# Power.net
KiCad netlist of a schematic drawn in Altium Designer
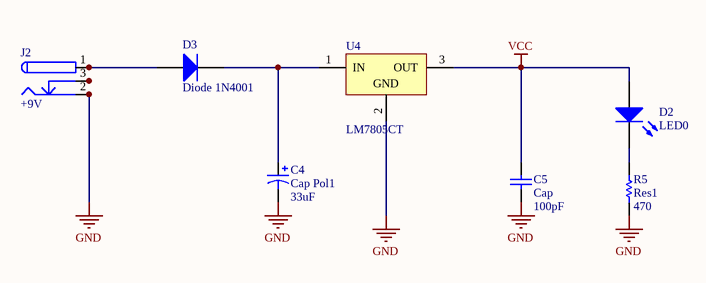
[diagram p0: Power.SchDoc]

(export (version "E")
  (design (tool "Eeschema 10.0.6"))
  (components
    (comp (ref "C4")
      (value "Cap Pol1")
      (footprint "RB7.6-15")
      (description "Polarized Capacitor (Radial)")
      (fields (field (name "ALTIUM_VALUE") "33uF") (field (name "PUBLISHER") "Altium Limited"))
      (libsource (lib "Chap-7-实践题(1)") (part "Cap Pol1"))
    )
    (comp (ref "C5")
      (value "Cap")
      (footprint "RAD-0.3")
      (description "Capacitor")
      (fields (field (name "ALTIUM_VALUE") "100pF") (field (name "PUBLISHER") "Altium Limited"))
      (libsource (lib "Chap-7-实践题(1)") (part "Cap"))
    )
    (comp (ref "D2")
      (value "LED0")
      (footprint "LED-0")
      (description "Typical INFRARED GaAs LED")
      (fields (field (name "PUBLISHER") "Altium Limited"))
      (libsource (lib "Chap-7-实践题(1)") (part "LED0"))
    )
    (comp (ref "D3")
      (value "Diode 1N4001")
      (footprint "DO-41")
      (description "1 Amp General Purpose Rectifier")
      (fields (field (name "PUBLISHER") "Altium Limited"))
      (libsource (lib "Chap-7-实践题(1)") (part "Diode 1N4001"))
    )
    (comp (ref "J2")
      (value "+9V")
      (footprint "KLD-0202")
      (description "Low Voltage Power Supply Connector")
      (fields (field (name "PUBLISHER") "Altium Limited"))
      (libsource (lib "Chap-7-实践题(1)") (part "PWR2.5"))
    )
    (comp (ref "R5")
      (value "Res1")
      (footprint "AXIAL-0.3")
      (description "Resistor")
      (fields (field (name "ALTIUM_VALUE") "470") (field (name "PUBLISHER") "Altium Limited"))
      (libsource (lib "Chap-7-实践题(1)") (part "Res1"))
    )
    (comp (ref "U4")
      (value "LM7805CT")
      (footprint "T03B")
      (description "Series 3-Terminal Positive Regulator")
      (fields (field (name "PUBLISHER") "Altium Limited"))
      (libsource (lib "Chap-7-实践题(1)") (part "LM7818CT"))
    )
  )
  (nets
    (net (code "1") (name "GND") (class "Default")
      (node (ref "C4") (pin "2") (pinfunction "2_2") (pintype "passive"))
      (node (ref "C5") (pin "1") (pinfunction "1_1") (pintype "passive"))
      (node (ref "J2") (pin "2") (pinfunction "2_2") (pintype "power_in"))
      (node (ref "J2") (pin "2A") (pinfunction "2A_2A") (pintype "power_in"))
      (node (ref "J2") (pin "2B") (pinfunction "2B_2B") (pintype "power_in"))
      (node (ref "R5") (pin "1") (pinfunction "1_1") (pintype "passive"))
      (node (ref "U4") (pin "2") (pinfunction "GND_2") (pintype "power_in"))
    )
    (net (code "2") (name "Net-(D2-K)") (class "Default")
      (node (ref "D2") (pin "2") (pinfunction "K_2") (pintype "passive"))
      (node (ref "R5") (pin "2") (pinfunction "2_2") (pintype "passive"))
    )
    (net (code "3") (name "Net-(D3-A)") (class "Default")
      (node (ref "D3") (pin "1") (pinfunction "A_1") (pintype "passive"))
      (node (ref "J2") (pin "1") (pinfunction "1_1") (pintype "power_in"))
      (node (ref "J2") (pin "1A") (pinfunction "1A_1A") (pintype "power_in"))
      (node (ref "J2") (pin "1B") (pinfunction "1B_1B") (pintype "power_in"))
    )
    (net (code "4") (name "Net-(D3-K)") (class "Default")
      (node (ref "C4") (pin "1") (pinfunction "1_1") (pintype "passive"))
      (node (ref "D3") (pin "2") (pinfunction "K_2") (pintype "passive"))
      (node (ref "U4") (pin "1") (pinfunction "IN_1") (pintype "power_in"))
    )
    (net (code "5") (name "Net-(J2-Pad3)") (class "Default")
      (node (ref "J2") (pin "3") (pinfunction "3_3") (pintype "power_in"))
      (node (ref "J2") (pin "3A") (pinfunction "3A_3A") (pintype "power_in"))
      (node (ref "J2") (pin "3B") (pinfunction "3B_3B") (pintype "power_in"))
    )
    (net (code "6") (name "VCC") (class "Default")
      (node (ref "C5") (pin "2") (pinfunction "2_2") (pintype "passive"))
      (node (ref "D2") (pin "1") (pinfunction "A_1") (pintype "passive"))
      (node (ref "U4") (pin "3") (pinfunction "OUT_3") (pintype "power_in"))
    )
  )
)
